# bqZUM_Power.net
KiCad netlist of a schematic drawn in Altium Designer
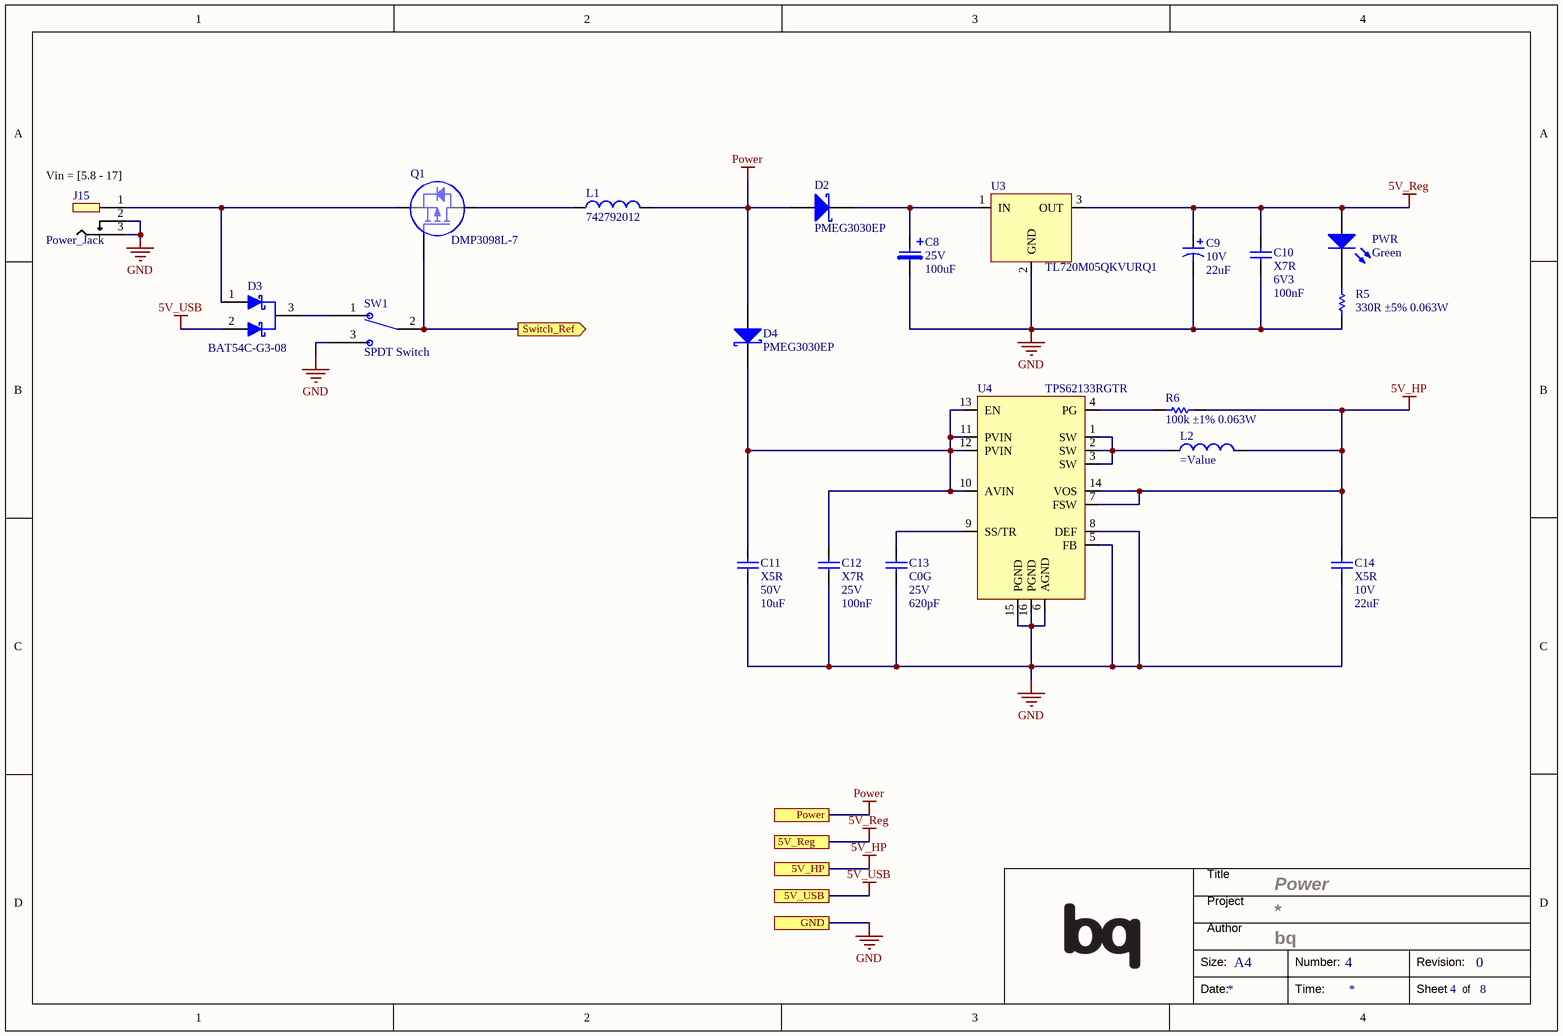
[diagram p0: bqZUM_Power.SchDoc]

(export (version "E")
  (design (tool "Eeschema 10.0.6"))
  (components
    (comp (ref "C8")
      (value "Electrolytic")
      (footprint "CASE_D_7.7")
      (description "Capacitor Electrolytic")
      (fields
        (field (name "VOLTAGE") "25V")
        (field (name "CAPACITANCE") "100uF")
        (field (name "PART NUMBER") "Cap_Al_100uF_25V")
        (field (name "MANUFACTURER") "Panasonic")
      )
      (libsource (lib "Pasives_Electrolytic_SMD") (part "Electrolytic"))
    )
    (comp (ref "C9")
      (value "Tantalum")
      (footprint "CASE_A_3216-1206")
      (description "Tantalum Capacitor")
      (fields
        (field (name "VOLTAGE") "10V")
        (field (name "CAPACITANCE") "22uF")
        (field (name "PART NUMBER") "22uF_10V_±20%")
        (field (name "TOLERANCE") "±20%")
      )
      (libsource (lib "Pasives_Tantal_SMD") (part "Tantalum"))
    )
    (comp (ref "C10")
      (value "Capacitor")
      (footprint "C0402")
      (fields
        (field (name "DIELECTRIC") "X7R")
        (field (name "VOLTAGE") "6V3")
        (field (name "CAPACITANCE") "100nF")
        (field (name "PART NUMBER") "C0402_100nF_6V3_±10%")
        (field (name "TOLERANCE") "±10%")
        (field (name "MANUFACTURER") "Kemet")
      )
      (libsource (lib "Pasives_Capacitor_SMD") (part "Capacitor"))
    )
    (comp (ref "C11")
      (value "Capacitor")
      (footprint "C1206")
      (fields
        (field (name "DIELECTRIC") "X5R")
        (field (name "VOLTAGE") "50V")
        (field (name "CAPACITANCE") "10uF")
        (field (name "PART NUMBER") "C1206_10uF_50V_±20%")
        (field (name "TOLERANCE") "±20%")
        (field (name "MANUFACTURER") "Taiyo Yuden")
      )
      (libsource (lib "Pasives_Capacitor_SMD") (part "Capacitor"))
    )
    (comp (ref "C12")
      (value "Capacitor")
      (footprint "C0603")
      (fields
        (field (name "DIELECTRIC") "X7R")
        (field (name "VOLTAGE") "25V")
        (field (name "CAPACITANCE") "100nF")
        (field (name "PART NUMBER") "C0603_100nF_25V_±10%")
        (field (name "TOLERANCE") "±10%")
        (field (name "MANUFACTURER") "Kemet")
      )
      (libsource (lib "Pasives_Capacitor_SMD") (part "Capacitor"))
    )
    (comp (ref "C13")
      (value "Capacitor")
      (footprint "C0603")
      (fields
        (field (name "DIELECTRIC") "C0G")
        (field (name "VOLTAGE") "25V")
        (field (name "CAPACITANCE") "620pF")
        (field (name "PART NUMBER") "C0603_620pF_25V_±5%")
        (field (name "TOLERANCE") "±5%")
        (field (name "MANUFACTURER") "Murata")
      )
      (libsource (lib "Pasives_Capacitor_SMD") (part "Capacitor"))
    )
    (comp (ref "C14")
      (value "Capacitor")
      (footprint "C1206")
      (fields
        (field (name "DIELECTRIC") "X5R")
        (field (name "VOLTAGE") "10V")
        (field (name "CAPACITANCE") "22uF")
        (field (name "PART NUMBER") "C1206_22uF_10V_±20%")
        (field (name "TOLERANCE") "±20%")
        (field (name "MANUFACTURER") "Taiyo Yuden")
      )
      (libsource (lib "Pasives_Capacitor_SMD") (part "Capacitor"))
    )
    (comp (ref "D2")
      (value "PMEG3030EP")
      (footprint "SOD128")
      (description "Diodo Schottky")
      (fields (field (name "MANUFACTURER") "NXP"))
      (libsource (lib "Semiconductors_Diodes") (part "Schottky"))
    )
    (comp (ref "D3")
      (value "BAT54C-G3-08")
      (footprint "SOT23-3")
      (description "Dual Schottky Diode Common Cathode")
      (fields (field (name "PART NUMBER") "BAT54C") (field (name "MANUFACTURER") "Vishay"))
      (libsource (lib "Semiconductors_Diodes") (part "Dual_Diode_Schottky_BAT54C"))
    )
    (comp (ref "D4")
      (value "PMEG3030EP")
      (footprint "SOD128")
      (description "Diodo Schottky")
      (fields (field (name "MANUFACTURER") "NXP"))
      (libsource (lib "Semiconductors_Diodes") (part "Schottky"))
    )
    (comp (ref "J15")
      (value "Power_Jack")
      (footprint "Jack 2.1")
      (description "DC Power Jack")
      (fields (field (name "MANUFACTURER") "Switchcraft"))
      (libsource (lib "Connectors_Power") (part "Power_Jack"))
    )
    (comp (ref "L1")
      (value "742792012")
      (footprint "L0805")
      (fields
        (field (name "PART NUMBER") "L0805_33R_0,008R_4000mA")
        (field (name "MANUFACTURER") "Würth Elektronik")
      )
      (libsource (lib "Pasivos_Inductor_SMD") (part "Ferrite Bead"))
    )
    (comp (ref "L2")
      (value "~")
      (footprint "SRN8040")
      (fields (field (name "PART NUMBER") "2,2uH_6,3A") (field (name "MANUFACTURER") "Bourns"))
      (libsource (lib "Pasivos_Inductor_SMD") (part "Inductor"))
    )
    (comp (ref "PWR")
      (value "Green")
      (footprint "LED0603")
      (description "Light Emitting Diode")
      (fields (field (name "PART NUMBER") "HSMG-C190") (field (name "MANUFACTURER") "Avago Technologies"))
      (libsource (lib "Optoelectronics") (part "LED"))
    )
    (comp (ref "Q1")
      (value "DMP3098L-7")
      (footprint "SOT23-3")
      (description "Mosfet Channel P Enhancement Mode")
      (fields (field (name "PART NUMBER") "DMP3098L") (field (name "MANUFACTURER") "Diodes Incorporated"))
      (libsource (lib "Semiconductors_Transistors") (part "Mosfet_P"))
    )
    (comp (ref "R5")
      (value "330R ±5% 0.063W")
      (footprint "R0402")
      (description "Resistor")
      (fields (field (name "TOLERANCE") "±5%") (field (name "POWER") "0.063W"))
      (libsource (lib "Pasives_Resistor_SMD") (part "Resistor"))
    )
    (comp (ref "R6")
      (value "100k ±1% 0.063W")
      (footprint "R0402")
      (description "Resistor")
      (fields (field (name "TOLERANCE") "±1%") (field (name "POWER") "0.063W"))
      (libsource (lib "Pasives_Resistor_SMD") (part "Resistor"))
    )
    (comp (ref "SW1")
      (value "SPDT Switch")
      (footprint "Slide SW SPDT Right Angle")
      (fields (field (name "PART NUMBER") "Switch SPDT") (field (name "MANUFACTURER") "Würth Elektronik"))
      (libsource (lib "Electromechanical") (part "SPDT Switch"))
    )
    (comp (ref "U3")
      (value "TL720M05QKVURQ1")
      (footprint "TO-252")
      (description "Standard 3pin LDO")
      (fields (field (name "PART NUMBER") "TL720M05-Q1") (field (name "MANUFACTURER") "Texas Instruments"))
      (libsource (lib "Power_Regulator") (part "LDO-3"))
    )
    (comp (ref "U4")
      (value "TPS62133RGTR")
      (footprint "QFN16")
      (description "3A High Efficient Synchronous Step Down Converter with DCS™ Control")
      (fields (field (name "PART NUMBER") "TPS62133") (field (name "MANUFACTURER") "Texas Instruments"))
      (libsource (lib "Power_Regulator") (part "TPS6213x"))
    )
  )
  (nets
    (net (code "1") (name "/Switch_Ref") (class "Default")
      (node (ref "Q1") (pin "1") (pinfunction "G_1") (pintype "passive"))
      (node (ref "SW1") (pin "2") (pinfunction "2_2") (pintype "passive"))
    )
    (net (code "2") (name "5V_HP") (class "Default")
      (node (ref "C14") (pin "2") (pinfunction "2_2") (pintype "passive"))
      (node (ref "L2") (pin "2") (pinfunction "2_2") (pintype "passive"))
      (node (ref "R6") (pin "2") (pinfunction "2_2") (pintype "passive"))
      (node (ref "U4") (pin "14") (pinfunction "VOS_14") (pintype "passive"))
      (node (ref "U4") (pin "7") (pinfunction "FSW_7") (pintype "passive"))
    )
    (net (code "3") (name "5V_Reg") (class "Default")
      (node (ref "C10") (pin "2") (pinfunction "2_2") (pintype "passive"))
      (node (ref "C9") (pin "1") (pinfunction "1_1") (pintype "passive"))
      (node (ref "PWR") (pin "A") (pinfunction "A_A") (pintype "passive"))
      (node (ref "U3") (pin "3") (pinfunction "OUT_3") (pintype "passive"))
    )
    (net (code "4") (name "5V_USB") (class "Default")
      (node (ref "D3") (pin "2") (pinfunction "A2_2") (pintype "passive"))
    )
    (net (code "5") (name "GND") (class "Default")
      (node (ref "C10") (pin "1") (pinfunction "1_1") (pintype "passive"))
      (node (ref "C11") (pin "1") (pinfunction "1_1") (pintype "passive"))
      (node (ref "C12") (pin "1") (pinfunction "1_1") (pintype "passive"))
      (node (ref "C13") (pin "1") (pinfunction "1_1") (pintype "passive"))
      (node (ref "C14") (pin "1") (pinfunction "1_1") (pintype "passive"))
      (node (ref "C8") (pin "2") (pinfunction "2_2") (pintype "passive"))
      (node (ref "C9") (pin "2") (pinfunction "2_2") (pintype "passive"))
      (node (ref "J15") (pin "2") (pinfunction "2_2") (pintype "passive"))
      (node (ref "J15") (pin "3") (pinfunction "3_3") (pintype "passive"))
      (node (ref "R5") (pin "1") (pinfunction "1_1") (pintype "passive"))
      (node (ref "SW1") (pin "3") (pinfunction "3_3") (pintype "passive"))
      (node (ref "U3") (pin "2") (pinfunction "GND_2") (pintype "passive"))
      (node (ref "U4") (pin "15") (pinfunction "PGND_15") (pintype "passive"))
      (node (ref "U4") (pin "16") (pinfunction "PGND_16") (pintype "passive"))
      (node (ref "U4") (pin "5") (pinfunction "FB_5") (pintype "passive"))
      (node (ref "U4") (pin "6") (pinfunction "AGND_6") (pintype "passive"))
      (node (ref "U4") (pin "8") (pinfunction "DEF_8") (pintype "passive"))
    )
    (net (code "6") (name "Net-(D2-K)") (class "Default")
      (node (ref "C8") (pin "1") (pinfunction "1_1") (pintype "passive"))
      (node (ref "D2") (pin "k") (pinfunction "K_k") (pintype "passive"))
      (node (ref "U3") (pin "1") (pinfunction "IN_1") (pintype "passive"))
    )
    (net (code "7") (name "Net-(D3-A1)") (class "Default")
      (node (ref "D3") (pin "1") (pinfunction "A1_1") (pintype "passive"))
      (node (ref "J15") (pin "1") (pinfunction "1_1") (pintype "passive"))
      (node (ref "Q1") (pin "2") (pinfunction "S_2") (pintype "passive"))
    )
    (net (code "8") (name "Net-(D3-K)") (class "Default")
      (node (ref "D3") (pin "3") (pinfunction "K_3") (pintype "passive"))
      (node (ref "SW1") (pin "1") (pinfunction "1_1") (pintype "passive"))
    )
    (net (code "9") (name "Net-(D4-K)") (class "Default")
      (node (ref "C11") (pin "2") (pinfunction "2_2") (pintype "passive"))
      (node (ref "C12") (pin "2") (pinfunction "2_2") (pintype "passive"))
      (node (ref "D4") (pin "k") (pinfunction "K_k") (pintype "passive"))
      (node (ref "U4") (pin "10") (pinfunction "AVIN_10") (pintype "passive"))
      (node (ref "U4") (pin "11") (pinfunction "PVIN_11") (pintype "passive"))
      (node (ref "U4") (pin "12") (pinfunction "PVIN_12") (pintype "passive"))
      (node (ref "U4") (pin "13") (pinfunction "EN_13") (pintype "passive"))
    )
    (net (code "10") (name "Net-(L2-Pad1)") (class "Default")
      (node (ref "L2") (pin "1") (pinfunction "1_1") (pintype "passive"))
      (node (ref "U4") (pin "1") (pinfunction "SW_1") (pintype "passive"))
      (node (ref "U4") (pin "2") (pinfunction "SW_2") (pintype "passive"))
      (node (ref "U4") (pin "3") (pinfunction "SW_3") (pintype "passive"))
    )
    (net (code "11") (name "Net-(PWR-PadK)") (class "Default")
      (node (ref "PWR") (pin "K") (pinfunction "K_K") (pintype "passive"))
      (node (ref "R5") (pin "2") (pinfunction "2_2") (pintype "passive"))
    )
    (net (code "12") (name "Net-(Q1-D)") (class "Default")
      (node (ref "L1") (pin "1") (pinfunction "1_1") (pintype "passive"))
      (node (ref "Q1") (pin "3") (pinfunction "D_3") (pintype "passive"))
    )
    (net (code "13") (name "Net-(U4-PG)") (class "Default")
      (node (ref "R6") (pin "1") (pinfunction "1_1") (pintype "passive"))
      (node (ref "U4") (pin "4") (pinfunction "PG_4") (pintype "passive"))
    )
    (net (code "14") (name "Net-(U4-SS{slash}TR)") (class "Default")
      (node (ref "C13") (pin "2") (pinfunction "2_2") (pintype "passive"))
      (node (ref "U4") (pin "9") (pinfunction "SS/TR_9") (pintype "passive"))
    )
    (net (code "15") (name "Power") (class "Default")
      (node (ref "D2") (pin "A") (pinfunction "A_A") (pintype "passive"))
      (node (ref "D4") (pin "A") (pinfunction "A_A") (pintype "passive"))
      (node (ref "L1") (pin "2") (pinfunction "2_2") (pintype "passive"))
    )
  )
)
